# RTDBank.net
KiCad netlist of a schematic drawn in Altium Designer
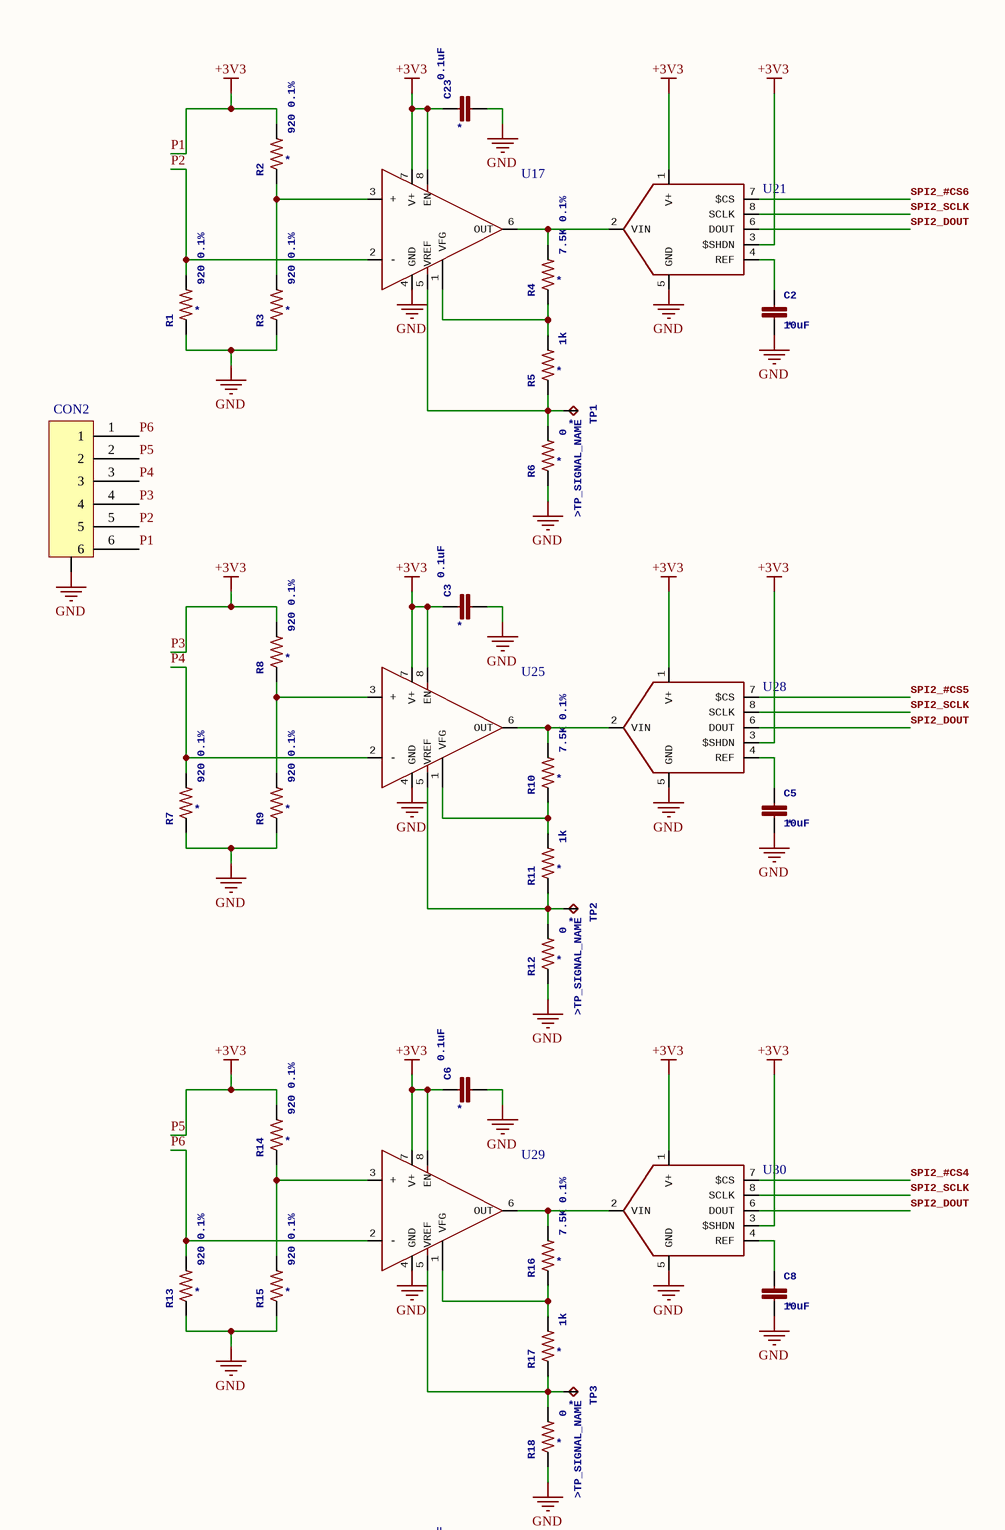
[diagram p0: RTDBank.SchDoc, top]
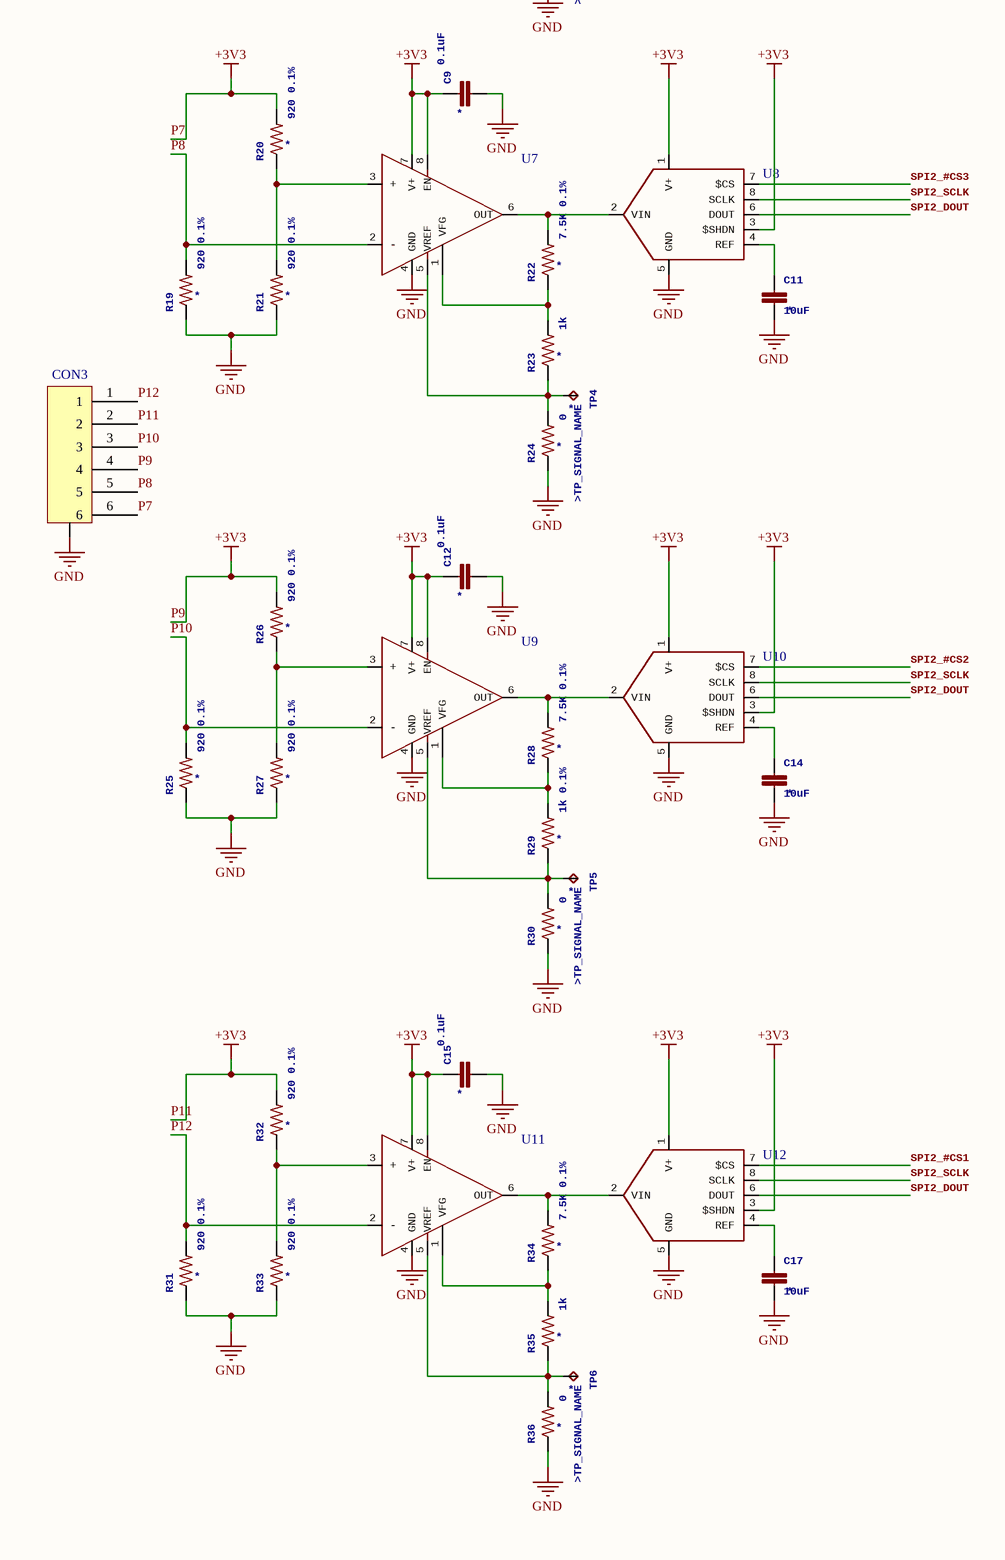
[diagram p1: RTDBank.SchDoc, bottom]

(export (version "E")
  (design (tool "Eeschema 10.0.6"))
  (components
    (comp (ref "C2")
      (value "10uF")
      (footprint "0603")
      (description "CAPACITOR, European symbol")
      (fields (field (name "NAME") "*"))
      (libsource (lib "rcl") (part "C-EUC0603K"))
    )
    (comp (ref "C3")
      (value "0.1uF")
      (footprint "0402 B")
      (description "CAPACITOR, European symbol")
      (fields (field (name "NAME") "*"))
      (libsource (lib "rcl") (part "C-EUC0402K"))
    )
    (comp (ref "C5")
      (value "10uF")
      (footprint "0603")
      (description "CAPACITOR, European symbol")
      (fields (field (name "NAME") "*"))
      (libsource (lib "rcl") (part "C-EUC0603K"))
    )
    (comp (ref "C6")
      (value "0.1uF")
      (footprint "0402 B")
      (description "CAPACITOR, European symbol")
      (fields (field (name "NAME") "*"))
      (libsource (lib "rcl") (part "C-EUC0402K"))
    )
    (comp (ref "C8")
      (value "10uF")
      (footprint "0603")
      (description "CAPACITOR, European symbol")
      (fields (field (name "NAME") "*"))
      (libsource (lib "rcl") (part "C-EUC0603K"))
    )
    (comp (ref "C9")
      (value "0.1uF")
      (footprint "0402 B")
      (description "CAPACITOR, European symbol")
      (fields (field (name "NAME") "*"))
      (libsource (lib "rcl") (part "C-EUC0402K"))
    )
    (comp (ref "C11")
      (value "10uF")
      (footprint "0603")
      (description "CAPACITOR, European symbol")
      (fields (field (name "NAME") "*"))
      (libsource (lib "rcl") (part "C-EUC0603K"))
    )
    (comp (ref "C12")
      (value "0.1uF")
      (footprint "0402 B")
      (description "CAPACITOR, European symbol")
      (fields (field (name "NAME") "*"))
      (libsource (lib "rcl") (part "C-EUC0402K"))
    )
    (comp (ref "C14")
      (value "10uF")
      (footprint "0603")
      (description "CAPACITOR, European symbol")
      (fields (field (name "NAME") "*"))
      (libsource (lib "rcl") (part "C-EUC0603K"))
    )
    (comp (ref "C15")
      (value "0.1uF")
      (footprint "0402 B")
      (description "CAPACITOR, European symbol")
      (fields (field (name "NAME") "*"))
      (libsource (lib "rcl") (part "C-EUC0402K"))
    )
    (comp (ref "C17")
      (value "10uF")
      (footprint "0603")
      (description "CAPACITOR, European symbol")
      (fields (field (name "NAME") "*"))
      (libsource (lib "rcl") (part "C-EUC0603K"))
    )
    (comp (ref "C23")
      (value "0.1uF")
      (footprint "0402 B")
      (description "CAPACITOR, European symbol")
      (fields (field (name "NAME") "*"))
      (libsource (lib "rcl") (part "C-EUC0402K"))
    )
    (comp (ref "CON2")
      (value "T1M-06-F-SH-L-K")
      (footprint "T1M-06-F-SH-L-K")
      (description "6 Positions Header Connector Surface Mount, Right Angle")
      (fields (field (name "MANUFACTURER") "Samtec"))
      (libsource (lib "DaughterBoard") (part "T1M-06-F-SH-L-K"))
    )
    (comp (ref "CON3")
      (value "T1M-06-F-SH-L-K")
      (footprint "T1M-06-F-SH-L-K")
      (description "6 Positions Header Connector Surface Mount, Right Angle")
      (fields (field (name "MANUFACTURER") "Samtec"))
      (libsource (lib "DaughterBoard") (part "T1M-06-F-SH-L-K"))
    )
    (comp (ref "R1")
      (value "920 0.1%")
      (footprint "0603R")
      (description "RESISTOR, American symbol")
      (fields (field (name "NAME") "*"))
      (libsource (lib "rcl") (part "R-US_R0603"))
    )
    (comp (ref "R2")
      (value "920 0.1%")
      (footprint "0603R")
      (description "RESISTOR, American symbol")
      (fields (field (name "NAME") "*"))
      (libsource (lib "rcl") (part "R-US_R0603"))
    )
    (comp (ref "R3")
      (value "920 0.1%")
      (footprint "0603R")
      (description "RESISTOR, American symbol")
      (fields (field (name "NAME") "*"))
      (libsource (lib "rcl") (part "R-US_R0603"))
    )
    (comp (ref "R4")
      (value "7.5K 0.1%")
      (footprint "0603R")
      (description "RESISTOR, American symbol")
      (fields (field (name "NAME") "*"))
      (libsource (lib "rcl") (part "R-US_R0603"))
    )
    (comp (ref "R5")
      (value "1k")
      (footprint "0603R")
      (description "RESISTOR, American symbol")
      (fields (field (name "NAME") "*"))
      (libsource (lib "rcl") (part "R-US_R0603"))
    )
    (comp (ref "R6")
      (value "0")
      (footprint "0603R")
      (description "RESISTOR, American symbol")
      (fields (field (name "NAME") "*"))
      (libsource (lib "rcl") (part "R-US_R0603"))
    )
    (comp (ref "R7")
      (value "920 0.1%")
      (footprint "0603R")
      (description "RESISTOR, American symbol")
      (fields (field (name "NAME") "*"))
      (libsource (lib "rcl") (part "R-US_R0603"))
    )
    (comp (ref "R8")
      (value "920 0.1%")
      (footprint "0603R")
      (description "RESISTOR, American symbol")
      (fields (field (name "NAME") "*"))
      (libsource (lib "rcl") (part "R-US_R0603"))
    )
    (comp (ref "R9")
      (value "920 0.1%")
      (footprint "0603R")
      (description "RESISTOR, American symbol")
      (fields (field (name "NAME") "*"))
      (libsource (lib "rcl") (part "R-US_R0603"))
    )
    (comp (ref "R10")
      (value "7.5K 0.1%")
      (footprint "0603R")
      (description "RESISTOR, American symbol")
      (fields (field (name "NAME") "*"))
      (libsource (lib "rcl") (part "R-US_R0603"))
    )
    (comp (ref "R11")
      (value "1k")
      (footprint "0603R")
      (description "RESISTOR, American symbol")
      (fields (field (name "NAME") "*"))
      (libsource (lib "rcl") (part "R-US_R0603"))
    )
    (comp (ref "R12")
      (value "0")
      (footprint "0603R")
      (description "RESISTOR, American symbol")
      (fields (field (name "NAME") "*"))
      (libsource (lib "rcl") (part "R-US_R0603"))
    )
    (comp (ref "R13")
      (value "920 0.1%")
      (footprint "0603R")
      (description "RESISTOR, American symbol")
      (fields (field (name "NAME") "*"))
      (libsource (lib "rcl") (part "R-US_R0603"))
    )
    (comp (ref "R14")
      (value "920 0.1%")
      (footprint "0603R")
      (description "RESISTOR, American symbol")
      (fields (field (name "NAME") "*"))
      (libsource (lib "rcl") (part "R-US_R0603"))
    )
    (comp (ref "R15")
      (value "920 0.1%")
      (footprint "0603R")
      (description "RESISTOR, American symbol")
      (fields (field (name "NAME") "*"))
      (libsource (lib "rcl") (part "R-US_R0603"))
    )
    (comp (ref "R16")
      (value "7.5K 0.1%")
      (footprint "0603R")
      (description "RESISTOR, American symbol")
      (fields (field (name "NAME") "*"))
      (libsource (lib "rcl") (part "R-US_R0603"))
    )
    (comp (ref "R17")
      (value "1k")
      (footprint "0603R")
      (description "RESISTOR, American symbol")
      (fields (field (name "NAME") "*"))
      (libsource (lib "rcl") (part "R-US_R0603"))
    )
    (comp (ref "R18")
      (value "0")
      (footprint "0603R")
      (description "RESISTOR, American symbol")
      (fields (field (name "NAME") "*"))
      (libsource (lib "rcl") (part "R-US_R0603"))
    )
    (comp (ref "R19")
      (value "920 0.1%")
      (footprint "0603R")
      (description "RESISTOR, American symbol")
      (fields (field (name "NAME") "*"))
      (libsource (lib "rcl") (part "R-US_R0603"))
    )
    (comp (ref "R20")
      (value "920 0.1%")
      (footprint "0603R")
      (description "RESISTOR, American symbol")
      (fields (field (name "NAME") "*"))
      (libsource (lib "rcl") (part "R-US_R0603"))
    )
    (comp (ref "R21")
      (value "920 0.1%")
      (footprint "0603R")
      (description "RESISTOR, American symbol")
      (fields (field (name "NAME") "*"))
      (libsource (lib "rcl") (part "R-US_R0603"))
    )
    (comp (ref "R22")
      (value "7.5K 0.1%")
      (footprint "0603R")
      (description "RESISTOR, American symbol")
      (fields (field (name "NAME") "*"))
      (libsource (lib "rcl") (part "R-US_R0603"))
    )
    (comp (ref "R23")
      (value "1k")
      (footprint "0603R")
      (description "RESISTOR, American symbol")
      (fields (field (name "NAME") "*"))
      (libsource (lib "rcl") (part "R-US_R0603"))
    )
    (comp (ref "R24")
      (value "0")
      (footprint "0603R")
      (description "RESISTOR, American symbol")
      (fields (field (name "NAME") "*"))
      (libsource (lib "rcl") (part "R-US_R0603"))
    )
    (comp (ref "R25")
      (value "920 0.1%")
      (footprint "0603R")
      (description "RESISTOR, American symbol")
      (fields (field (name "NAME") "*"))
      (libsource (lib "rcl") (part "R-US_R0603"))
    )
    (comp (ref "R26")
      (value "920 0.1%")
      (footprint "0603R")
      (description "RESISTOR, American symbol")
      (fields (field (name "NAME") "*"))
      (libsource (lib "rcl") (part "R-US_R0603"))
    )
    (comp (ref "R27")
      (value "920 0.1%")
      (footprint "0603R")
      (description "RESISTOR, American symbol")
      (fields (field (name "NAME") "*"))
      (libsource (lib "rcl") (part "R-US_R0603"))
    )
    (comp (ref "R28")
      (value "7.5K 0.1%")
      (footprint "0603R")
      (description "RESISTOR, American symbol")
      (fields (field (name "NAME") "*"))
      (libsource (lib "rcl") (part "R-US_R0603"))
    )
    (comp (ref "R29")
      (value "1k 0.1%")
      (footprint "0603R")
      (description "RESISTOR, American symbol")
      (fields (field (name "NAME") "*"))
      (libsource (lib "rcl") (part "R-US_R0603"))
    )
    (comp (ref "R30")
      (value "0")
      (footprint "0603R")
      (description "RESISTOR, American symbol")
      (fields (field (name "NAME") "*"))
      (libsource (lib "rcl") (part "R-US_R0603"))
    )
    (comp (ref "R31")
      (value "920 0.1%")
      (footprint "0603R")
      (description "RESISTOR, American symbol")
      (fields (field (name "NAME") "*"))
      (libsource (lib "rcl") (part "R-US_R0603"))
    )
    (comp (ref "R32")
      (value "920 0.1%")
      (footprint "0603R")
      (description "RESISTOR, American symbol")
      (fields (field (name "NAME") "*"))
      (libsource (lib "rcl") (part "R-US_R0603"))
    )
    (comp (ref "R33")
      (value "920 0.1%")
      (footprint "0603R")
      (description "RESISTOR, American symbol")
      (fields (field (name "NAME") "*"))
      (libsource (lib "rcl") (part "R-US_R0603"))
    )
    (comp (ref "R34")
      (value "7.5K 0.1%")
      (footprint "0603R")
      (description "RESISTOR, American symbol")
      (fields (field (name "NAME") "*"))
      (libsource (lib "rcl") (part "R-US_R0603"))
    )
    (comp (ref "R35")
      (value "1k")
      (footprint "0603R")
      (description "RESISTOR, American symbol")
      (fields (field (name "NAME") "*"))
      (libsource (lib "rcl") (part "R-US_R0603"))
    )
    (comp (ref "R36")
      (value "0")
      (footprint "0603R")
      (description "RESISTOR, American symbol")
      (fields (field (name "NAME") "*"))
      (libsource (lib "rcl") (part "R-US_R0603"))
    )
    (comp (ref "TP1")
      (value "TPB1,27")
      (footprint "B1,27")
      (description "Test pad")
      (fields
        (field (name "NAME") "*")
        (field (name "TP_SIGNAL_NAME") ">TP_SIGNAL_NAME")
        (field (name "LIBRARYNAME") "testpad")
      )
      (libsource (lib "testpad") (part "TPB1,27"))
    )
    (comp (ref "TP2")
      (value "TPB1,27")
      (footprint "B1,27")
      (description "Test pad")
      (fields
        (field (name "NAME") "*")
        (field (name "TP_SIGNAL_NAME") ">TP_SIGNAL_NAME")
        (field (name "LIBRARYNAME") "testpad")
      )
      (libsource (lib "testpad") (part "TPB1,27"))
    )
    (comp (ref "TP3")
      (value "TPB1,27")
      (footprint "B1,27")
      (description "Test pad")
      (fields
        (field (name "NAME") "*")
        (field (name "TP_SIGNAL_NAME") ">TP_SIGNAL_NAME")
        (field (name "LIBRARYNAME") "testpad")
      )
      (libsource (lib "testpad") (part "TPB1,27"))
    )
    (comp (ref "TP4")
      (value "TPB1,27")
      (footprint "B1,27")
      (description "Test pad")
      (fields
        (field (name "NAME") "*")
        (field (name "TP_SIGNAL_NAME") ">TP_SIGNAL_NAME")
        (field (name "LIBRARYNAME") "testpad")
      )
      (libsource (lib "testpad") (part "TPB1,27"))
    )
    (comp (ref "TP5")
      (value "TPB1,27")
      (footprint "B1,27")
      (description "Test pad")
      (fields
        (field (name "NAME") "*")
        (field (name "TP_SIGNAL_NAME") ">TP_SIGNAL_NAME")
        (field (name "LIBRARYNAME") "testpad")
      )
      (libsource (lib "testpad") (part "TPB1,27"))
    )
    (comp (ref "TP6")
      (value "TPB1,27")
      (footprint "B1,27")
      (description "Test pad")
      (fields
        (field (name "NAME") "*")
        (field (name "TP_SIGNAL_NAME") ">TP_SIGNAL_NAME")
        (field (name "LIBRARYNAME") "testpad")
      )
      (libsource (lib "testpad") (part "TPB1,27"))
    )
    (comp (ref "U7") (value "MCP6N11") (footprint "SOIC8") (libsource (lib "custom") (part "MCP6N11")))
    (comp (ref "U8") (value "MAX1240") (footprint "SOIC8") (libsource (lib "custom") (part "MAX1240")))
    (comp (ref "U9") (value "MCP6N11") (footprint "SOIC8") (libsource (lib "custom") (part "MCP6N11")))
    (comp (ref "U10") (value "MAX1240") (footprint "SOIC8") (libsource (lib "custom") (part "MAX1240")))
    (comp (ref "U11") (value "MCP6N11") (footprint "SOIC8") (libsource (lib "custom") (part "MCP6N11")))
    (comp (ref "U12") (value "MAX1240") (footprint "SOIC8") (libsource (lib "custom") (part "MAX1240")))
    (comp (ref "U17") (value "MCP6N11") (footprint "SOIC8") (libsource (lib "custom") (part "MCP6N11")))
    (comp (ref "U21") (value "MAX1240") (footprint "SOIC8") (libsource (lib "custom") (part "MAX1240")))
    (comp (ref "U25") (value "MCP6N11") (footprint "SOIC8") (libsource (lib "custom") (part "MCP6N11")))
    (comp (ref "U28") (value "MAX1240") (footprint "SOIC8") (libsource (lib "custom") (part "MAX1240")))
    (comp (ref "U29") (value "MCP6N11") (footprint "SOIC8") (libsource (lib "custom") (part "MCP6N11")))
    (comp (ref "U30") (value "MAX1240") (footprint "SOIC8") (libsource (lib "custom") (part "MAX1240")))
  )
  (nets
    (net (code "1") (name "+3V3") (class "Default")
      (node (ref "C12") (pin "1") (pinfunction "1_1") (pintype "passive"))
      (node (ref "C15") (pin "1") (pinfunction "1_1") (pintype "passive"))
      (node (ref "C23") (pin "1") (pinfunction "1_1") (pintype "passive"))
      (node (ref "C3") (pin "1") (pinfunction "1_1") (pintype "passive"))
      (node (ref "C6") (pin "1") (pinfunction "1_1") (pintype "passive"))
      (node (ref "C9") (pin "1") (pinfunction "1_1") (pintype "passive"))
      (node (ref "CON2") (pin "2") (pinfunction "2_2") (pintype "passive"))
      (node (ref "CON2") (pin "4") (pinfunction "4_4") (pintype "passive"))
      (node (ref "CON2") (pin "6") (pinfunction "6_6") (pintype "passive"))
      (node (ref "CON3") (pin "2") (pinfunction "2_2") (pintype "passive"))
      (node (ref "CON3") (pin "4") (pinfunction "4_4") (pintype "passive"))
      (node (ref "CON3") (pin "6") (pinfunction "6_6") (pintype "passive"))
      (node (ref "R14") (pin "2") (pinfunction "2_2") (pintype "passive"))
      (node (ref "R2") (pin "2") (pinfunction "2_2") (pintype "passive"))
      (node (ref "R20") (pin "2") (pinfunction "2_2") (pintype "passive"))
      (node (ref "R26") (pin "2") (pinfunction "2_2") (pintype "passive"))
      (node (ref "R32") (pin "2") (pinfunction "2_2") (pintype "passive"))
      (node (ref "R8") (pin "2") (pinfunction "2_2") (pintype "passive"))
      (node (ref "U10") (pin "1") (pinfunction "V+_1") (pintype "passive"))
      (node (ref "U10") (pin "3") (pinfunction "$SHDN_3") (pintype "passive"))
      (node (ref "U11") (pin "7") (pinfunction "V+_7") (pintype "passive"))
      (node (ref "U11") (pin "8") (pinfunction "EN_8") (pintype "passive"))
      (node (ref "U12") (pin "1") (pinfunction "V+_1") (pintype "passive"))
      (node (ref "U12") (pin "3") (pinfunction "$SHDN_3") (pintype "passive"))
      (node (ref "U17") (pin "7") (pinfunction "V+_7") (pintype "passive"))
      (node (ref "U17") (pin "8") (pinfunction "EN_8") (pintype "passive"))
      (node (ref "U21") (pin "1") (pinfunction "V+_1") (pintype "passive"))
      (node (ref "U21") (pin "3") (pinfunction "$SHDN_3") (pintype "passive"))
      (node (ref "U25") (pin "7") (pinfunction "V+_7") (pintype "passive"))
      (node (ref "U25") (pin "8") (pinfunction "EN_8") (pintype "passive"))
      (node (ref "U28") (pin "1") (pinfunction "V+_1") (pintype "passive"))
      (node (ref "U28") (pin "3") (pinfunction "$SHDN_3") (pintype "passive"))
      (node (ref "U29") (pin "7") (pinfunction "V+_7") (pintype "passive"))
      (node (ref "U29") (pin "8") (pinfunction "EN_8") (pintype "passive"))
      (node (ref "U30") (pin "1") (pinfunction "V+_1") (pintype "passive"))
      (node (ref "U30") (pin "3") (pinfunction "$SHDN_3") (pintype "passive"))
      (node (ref "U7") (pin "7") (pinfunction "V+_7") (pintype "passive"))
      (node (ref "U7") (pin "8") (pinfunction "EN_8") (pintype "passive"))
      (node (ref "U8") (pin "1") (pinfunction "V+_1") (pintype "passive"))
      (node (ref "U8") (pin "3") (pinfunction "$SHDN_3") (pintype "passive"))
      (node (ref "U9") (pin "7") (pinfunction "V+_7") (pintype "passive"))
      (node (ref "U9") (pin "8") (pinfunction "EN_8") (pintype "passive"))
    )
    (net (code "2") (name "/P2") (class "Default")
      (node (ref "CON2") (pin "5") (pinfunction "5_5") (pintype "passive"))
      (node (ref "R1") (pin "2") (pinfunction "2_2") (pintype "passive"))
      (node (ref "U17") (pin "2") (pinfunction "-_2") (pintype "passive"))
    )
    (net (code "3") (name "/P4") (class "Default")
      (node (ref "CON2") (pin "3") (pinfunction "3_3") (pintype "passive"))
      (node (ref "R7") (pin "2") (pinfunction "2_2") (pintype "passive"))
      (node (ref "U25") (pin "2") (pinfunction "-_2") (pintype "passive"))
    )
    (net (code "4") (name "/P6") (class "Default")
      (node (ref "CON2") (pin "1") (pinfunction "1_1") (pintype "passive"))
      (node (ref "R13") (pin "2") (pinfunction "2_2") (pintype "passive"))
      (node (ref "U29") (pin "2") (pinfunction "-_2") (pintype "passive"))
    )
    (net (code "5") (name "/P8") (class "Default")
      (node (ref "CON3") (pin "5") (pinfunction "5_5") (pintype "passive"))
      (node (ref "R19") (pin "2") (pinfunction "2_2") (pintype "passive"))
      (node (ref "U7") (pin "2") (pinfunction "-_2") (pintype "passive"))
    )
    (net (code "6") (name "/P10") (class "Default")
      (node (ref "CON3") (pin "3") (pinfunction "3_3") (pintype "passive"))
      (node (ref "R25") (pin "2") (pinfunction "2_2") (pintype "passive"))
      (node (ref "U9") (pin "2") (pinfunction "-_2") (pintype "passive"))
    )
    (net (code "7") (name "/P12") (class "Default")
      (node (ref "CON3") (pin "1") (pinfunction "1_1") (pintype "passive"))
      (node (ref "R31") (pin "2") (pinfunction "2_2") (pintype "passive"))
      (node (ref "U11") (pin "2") (pinfunction "-_2") (pintype "passive"))
    )
    (net (code "8") (name "/SPI2_#CS1") (class "Default")
      (node (ref "U12") (pin "7") (pinfunction "$CS_7") (pintype "passive"))
    )
    (net (code "9") (name "/SPI2_#CS2") (class "Default")
      (node (ref "U10") (pin "7") (pinfunction "$CS_7") (pintype "passive"))
    )
    (net (code "10") (name "/SPI2_#CS3") (class "Default")
      (node (ref "U8") (pin "7") (pinfunction "$CS_7") (pintype "passive"))
    )
    (net (code "11") (name "/SPI2_#CS4") (class "Default")
      (node (ref "U30") (pin "7") (pinfunction "$CS_7") (pintype "passive"))
    )
    (net (code "12") (name "/SPI2_#CS5") (class "Default")
      (node (ref "U28") (pin "7") (pinfunction "$CS_7") (pintype "passive"))
    )
    (net (code "13") (name "/SPI2_#CS6") (class "Default")
      (node (ref "U21") (pin "7") (pinfunction "$CS_7") (pintype "passive"))
    )
    (net (code "14") (name "/SPI2_DOUT") (class "Default")
      (node (ref "U10") (pin "6") (pinfunction "DOUT_6") (pintype "passive"))
      (node (ref "U12") (pin "6") (pinfunction "DOUT_6") (pintype "passive"))
      (node (ref "U21") (pin "6") (pinfunction "DOUT_6") (pintype "passive"))
      (node (ref "U28") (pin "6") (pinfunction "DOUT_6") (pintype "passive"))
      (node (ref "U30") (pin "6") (pinfunction "DOUT_6") (pintype "passive"))
      (node (ref "U8") (pin "6") (pinfunction "DOUT_6") (pintype "passive"))
    )
    (net (code "15") (name "/SPI2_SCLK") (class "Default")
      (node (ref "U10") (pin "8") (pinfunction "SCLK_8") (pintype "passive"))
      (node (ref "U12") (pin "8") (pinfunction "SCLK_8") (pintype "passive"))
      (node (ref "U21") (pin "8") (pinfunction "SCLK_8") (pintype "passive"))
      (node (ref "U28") (pin "8") (pinfunction "SCLK_8") (pintype "passive"))
      (node (ref "U30") (pin "8") (pinfunction "SCLK_8") (pintype "passive"))
      (node (ref "U8") (pin "8") (pinfunction "SCLK_8") (pintype "passive"))
    )
    (net (code "16") (name "GND") (class "Default")
      (node (ref "C11") (pin "2") (pinfunction "2_2") (pintype "passive"))
      (node (ref "C12") (pin "2") (pinfunction "2_2") (pintype "passive"))
      (node (ref "C14") (pin "2") (pinfunction "2_2") (pintype "passive"))
      (node (ref "C15") (pin "2") (pinfunction "2_2") (pintype "passive"))
      (node (ref "C17") (pin "2") (pinfunction "2_2") (pintype "passive"))
      (node (ref "C2") (pin "2") (pinfunction "2_2") (pintype "passive"))
      (node (ref "C23") (pin "2") (pinfunction "2_2") (pintype "passive"))
      (node (ref "C3") (pin "2") (pinfunction "2_2") (pintype "passive"))
      (node (ref "C5") (pin "2") (pinfunction "2_2") (pintype "passive"))
      (node (ref "C6") (pin "2") (pinfunction "2_2") (pintype "passive"))
      (node (ref "C8") (pin "2") (pinfunction "2_2") (pintype "passive"))
      (node (ref "C9") (pin "2") (pinfunction "2_2") (pintype "passive"))
      (node (ref "CON2") (pin "GND") (pinfunction "GND_GND") (pintype "passive"))
      (node (ref "CON3") (pin "GND") (pinfunction "GND_GND") (pintype "passive"))
      (node (ref "R1") (pin "1") (pinfunction "1_1") (pintype "passive"))
      (node (ref "R12") (pin "1") (pinfunction "1_1") (pintype "passive"))
      (node (ref "R13") (pin "1") (pinfunction "1_1") (pintype "passive"))
      (node (ref "R15") (pin "1") (pinfunction "1_1") (pintype "passive"))
      (node (ref "R18") (pin "1") (pinfunction "1_1") (pintype "passive"))
      (node (ref "R19") (pin "1") (pinfunction "1_1") (pintype "passive"))
      (node (ref "R21") (pin "1") (pinfunction "1_1") (pintype "passive"))
      (node (ref "R24") (pin "1") (pinfunction "1_1") (pintype "passive"))
      (node (ref "R25") (pin "1") (pinfunction "1_1") (pintype "passive"))
      (node (ref "R27") (pin "1") (pinfunction "1_1") (pintype "passive"))
      (node (ref "R3") (pin "1") (pinfunction "1_1") (pintype "passive"))
      (node (ref "R30") (pin "1") (pinfunction "1_1") (pintype "passive"))
      (node (ref "R31") (pin "1") (pinfunction "1_1") (pintype "passive"))
      (node (ref "R33") (pin "1") (pinfunction "1_1") (pintype "passive"))
      (node (ref "R36") (pin "1") (pinfunction "1_1") (pintype "passive"))
      (node (ref "R6") (pin "1") (pinfunction "1_1") (pintype "passive"))
      (node (ref "R7") (pin "1") (pinfunction "1_1") (pintype "passive"))
      (node (ref "R9") (pin "1") (pinfunction "1_1") (pintype "passive"))
      (node (ref "U10") (pin "5") (pinfunction "GND_5") (pintype "passive"))
      (node (ref "U11") (pin "4") (pinfunction "GND_4") (pintype "passive"))
      (node (ref "U12") (pin "5") (pinfunction "GND_5") (pintype "passive"))
      (node (ref "U17") (pin "4") (pinfunction "GND_4") (pintype "passive"))
      (node (ref "U21") (pin "5") (pinfunction "GND_5") (pintype "passive"))
      (node (ref "U25") (pin "4") (pinfunction "GND_4") (pintype "passive"))
      (node (ref "U28") (pin "5") (pinfunction "GND_5") (pintype "passive"))
      (node (ref "U29") (pin "4") (pinfunction "GND_4") (pintype "passive"))
      (node (ref "U30") (pin "5") (pinfunction "GND_5") (pintype "passive"))
      (node (ref "U7") (pin "4") (pinfunction "GND_4") (pintype "passive"))
      (node (ref "U8") (pin "5") (pinfunction "GND_5") (pintype "passive"))
      (node (ref "U9") (pin "4") (pinfunction "GND_4") (pintype "passive"))
    )
    (net (code "17") (name "Net-(U7-+)") (class "Default")
      (node (ref "R20") (pin "1") (pinfunction "1_1") (pintype "passive"))
      (node (ref "R21") (pin "2") (pinfunction "2_2") (pintype "passive"))
      (node (ref "U7") (pin "3") (pinfunction "+_3") (pintype "passive"))
    )
    (net (code "18") (name "Net-(U7-OUT)") (class "Default")
      (node (ref "R22") (pin "2") (pinfunction "2_2") (pintype "passive"))
      (node (ref "U7") (pin "6") (pinfunction "OUT_6") (pintype "passive"))
      (node (ref "U8") (pin "2") (pinfunction "VIN_2") (pintype "passive"))
    )
    (net (code "19") (name "Net-(U7-VFG)") (class "Default")
      (node (ref "R22") (pin "1") (pinfunction "1_1") (pintype "passive"))
      (node (ref "R23") (pin "2") (pinfunction "2_2") (pintype "passive"))
      (node (ref "U7") (pin "1") (pinfunction "VFG_1") (pintype "passive"))
    )
    (net (code "20") (name "Net-(U7-VREF)") (class "Default")
      (node (ref "R23") (pin "1") (pinfunction "1_1") (pintype "passive"))
      (node (ref "R24") (pin "2") (pinfunction "2_2") (pintype "passive"))
      (node (ref "TP4") (pin "TP") (pinfunction "TP_TP") (pintype "passive"))
      (node (ref "U7") (pin "5") (pinfunction "VREF_5") (pintype "passive"))
    )
    (net (code "21") (name "Net-(U8-REF)") (class "Default")
      (node (ref "C11") (pin "1") (pinfunction "1_1") (pintype "passive"))
      (node (ref "U8") (pin "4") (pinfunction "REF_4") (pintype "passive"))
    )
    (net (code "22") (name "Net-(U9-+)") (class "Default")
      (node (ref "R26") (pin "1") (pinfunction "1_1") (pintype "passive"))
      (node (ref "R27") (pin "2") (pinfunction "2_2") (pintype "passive"))
      (node (ref "U9") (pin "3") (pinfunction "+_3") (pintype "passive"))
    )
    (net (code "23") (name "Net-(U9-VFG)") (class "Default")
      (node (ref "R28") (pin "1") (pinfunction "1_1") (pintype "passive"))
      (node (ref "R29") (pin "2") (pinfunction "2_2") (pintype "passive"))
      (node (ref "U9") (pin "1") (pinfunction "VFG_1") (pintype "passive"))
    )
    (net (code "24") (name "Net-(U9-VREF)") (class "Default")
      (node (ref "R29") (pin "1") (pinfunction "1_1") (pintype "passive"))
      (node (ref "R30") (pin "2") (pinfunction "2_2") (pintype "passive"))
      (node (ref "TP5") (pin "TP") (pinfunction "TP_TP") (pintype "passive"))
      (node (ref "U9") (pin "5") (pinfunction "VREF_5") (pintype "passive"))
    )
    (net (code "25") (name "Net-(U10-REF)") (class "Default")
      (node (ref "C14") (pin "1") (pinfunction "1_1") (pintype "passive"))
      (node (ref "U10") (pin "4") (pinfunction "REF_4") (pintype "passive"))
    )
    (net (code "26") (name "Net-(U10-VIN)") (class "Default")
      (node (ref "R28") (pin "2") (pinfunction "2_2") (pintype "passive"))
      (node (ref "U10") (pin "2") (pinfunction "VIN_2") (pintype "passive"))
      (node (ref "U9") (pin "6") (pinfunction "OUT_6") (pintype "passive"))
    )
    (net (code "27") (name "Net-(U11-+)") (class "Default")
      (node (ref "R32") (pin "1") (pinfunction "1_1") (pintype "passive"))
      (node (ref "R33") (pin "2") (pinfunction "2_2") (pintype "passive"))
      (node (ref "U11") (pin "3") (pinfunction "+_3") (pintype "passive"))
    )
    (net (code "28") (name "Net-(U11-OUT)") (class "Default")
      (node (ref "R34") (pin "2") (pinfunction "2_2") (pintype "passive"))
      (node (ref "U11") (pin "6") (pinfunction "OUT_6") (pintype "passive"))
      (node (ref "U12") (pin "2") (pinfunction "VIN_2") (pintype "passive"))
    )
    (net (code "29") (name "Net-(U11-VFG)") (class "Default")
      (node (ref "R34") (pin "1") (pinfunction "1_1") (pintype "passive"))
      (node (ref "R35") (pin "2") (pinfunction "2_2") (pintype "passive"))
      (node (ref "U11") (pin "1") (pinfunction "VFG_1") (pintype "passive"))
    )
    (net (code "30") (name "Net-(U11-VREF)") (class "Default")
      (node (ref "R35") (pin "1") (pinfunction "1_1") (pintype "passive"))
      (node (ref "R36") (pin "2") (pinfunction "2_2") (pintype "passive"))
      (node (ref "TP6") (pin "TP") (pinfunction "TP_TP") (pintype "passive"))
      (node (ref "U11") (pin "5") (pinfunction "VREF_5") (pintype "passive"))
    )
    (net (code "31") (name "Net-(U12-REF)") (class "Default")
      (node (ref "C17") (pin "1") (pinfunction "1_1") (pintype "passive"))
      (node (ref "U12") (pin "4") (pinfunction "REF_4") (pintype "passive"))
    )
    (net (code "32") (name "Net-(U17-+)") (class "Default")
      (node (ref "R2") (pin "1") (pinfunction "1_1") (pintype "passive"))
      (node (ref "R3") (pin "2") (pinfunction "2_2") (pintype "passive"))
      (node (ref "U17") (pin "3") (pinfunction "+_3") (pintype "passive"))
    )
    (net (code "33") (name "Net-(U17-OUT)") (class "Default")
      (node (ref "R4") (pin "2") (pinfunction "2_2") (pintype "passive"))
      (node (ref "U17") (pin "6") (pinfunction "OUT_6") (pintype "passive"))
      (node (ref "U21") (pin "2") (pinfunction "VIN_2") (pintype "passive"))
    )
    (net (code "34") (name "Net-(U17-VFG)") (class "Default")
      (node (ref "R4") (pin "1") (pinfunction "1_1") (pintype "passive"))
      (node (ref "R5") (pin "2") (pinfunction "2_2") (pintype "passive"))
      (node (ref "U17") (pin "1") (pinfunction "VFG_1") (pintype "passive"))
    )
    (net (code "35") (name "Net-(U17-VREF)") (class "Default")
      (node (ref "R5") (pin "1") (pinfunction "1_1") (pintype "passive"))
      (node (ref "R6") (pin "2") (pinfunction "2_2") (pintype "passive"))
      (node (ref "TP1") (pin "TP") (pinfunction "TP_TP") (pintype "passive"))
      (node (ref "U17") (pin "5") (pinfunction "VREF_5") (pintype "passive"))
    )
    (net (code "36") (name "Net-(U21-REF)") (class "Default")
      (node (ref "C2") (pin "1") (pinfunction "1_1") (pintype "passive"))
      (node (ref "U21") (pin "4") (pinfunction "REF_4") (pintype "passive"))
    )
    (net (code "37") (name "Net-(U25-+)") (class "Default")
      (node (ref "R8") (pin "1") (pinfunction "1_1") (pintype "passive"))
      (node (ref "R9") (pin "2") (pinfunction "2_2") (pintype "passive"))
      (node (ref "U25") (pin "3") (pinfunction "+_3") (pintype "passive"))
    )
    (net (code "38") (name "Net-(U25-OUT)") (class "Default")
      (node (ref "R10") (pin "2") (pinfunction "2_2") (pintype "passive"))
      (node (ref "U25") (pin "6") (pinfunction "OUT_6") (pintype "passive"))
      (node (ref "U28") (pin "2") (pinfunction "VIN_2") (pintype "passive"))
    )
    (net (code "39") (name "Net-(U25-VFG)") (class "Default")
      (node (ref "R10") (pin "1") (pinfunction "1_1") (pintype "passive"))
      (node (ref "R11") (pin "2") (pinfunction "2_2") (pintype "passive"))
      (node (ref "U25") (pin "1") (pinfunction "VFG_1") (pintype "passive"))
    )
    (net (code "40") (name "Net-(U25-VREF)") (class "Default")
      (node (ref "R11") (pin "1") (pinfunction "1_1") (pintype "passive"))
      (node (ref "R12") (pin "2") (pinfunction "2_2") (pintype "passive"))
      (node (ref "TP2") (pin "TP") (pinfunction "TP_TP") (pintype "passive"))
      (node (ref "U25") (pin "5") (pinfunction "VREF_5") (pintype "passive"))
    )
    (net (code "41") (name "Net-(U28-REF)") (class "Default")
      (node (ref "C5") (pin "1") (pinfunction "1_1") (pintype "passive"))
      (node (ref "U28") (pin "4") (pinfunction "REF_4") (pintype "passive"))
    )
    (net (code "42") (name "Net-(U29-+)") (class "Default")
      (node (ref "R14") (pin "1") (pinfunction "1_1") (pintype "passive"))
      (node (ref "R15") (pin "2") (pinfunction "2_2") (pintype "passive"))
      (node (ref "U29") (pin "3") (pinfunction "+_3") (pintype "passive"))
    )
    (net (code "43") (name "Net-(U29-OUT)") (class "Default")
      (node (ref "R16") (pin "2") (pinfunction "2_2") (pintype "passive"))
      (node (ref "U29") (pin "6") (pinfunction "OUT_6") (pintype "passive"))
      (node (ref "U30") (pin "2") (pinfunction "VIN_2") (pintype "passive"))
    )
    (net (code "44") (name "Net-(U29-VFG)") (class "Default")
      (node (ref "R16") (pin "1") (pinfunction "1_1") (pintype "passive"))
      (node (ref "R17") (pin "2") (pinfunction "2_2") (pintype "passive"))
      (node (ref "U29") (pin "1") (pinfunction "VFG_1") (pintype "passive"))
    )
    (net (code "45") (name "Net-(U29-VREF)") (class "Default")
      (node (ref "R17") (pin "1") (pinfunction "1_1") (pintype "passive"))
      (node (ref "R18") (pin "2") (pinfunction "2_2") (pintype "passive"))
      (node (ref "TP3") (pin "TP") (pinfunction "TP_TP") (pintype "passive"))
      (node (ref "U29") (pin "5") (pinfunction "VREF_5") (pintype "passive"))
    )
    (net (code "46") (name "Net-(U30-REF)") (class "Default")
      (node (ref "C8") (pin "1") (pinfunction "1_1") (pintype "passive"))
      (node (ref "U30") (pin "4") (pinfunction "REF_4") (pintype "passive"))
    )
  )
)
